# MCU_buck.net
KiCad netlist of a schematic drawn in Altium Designer
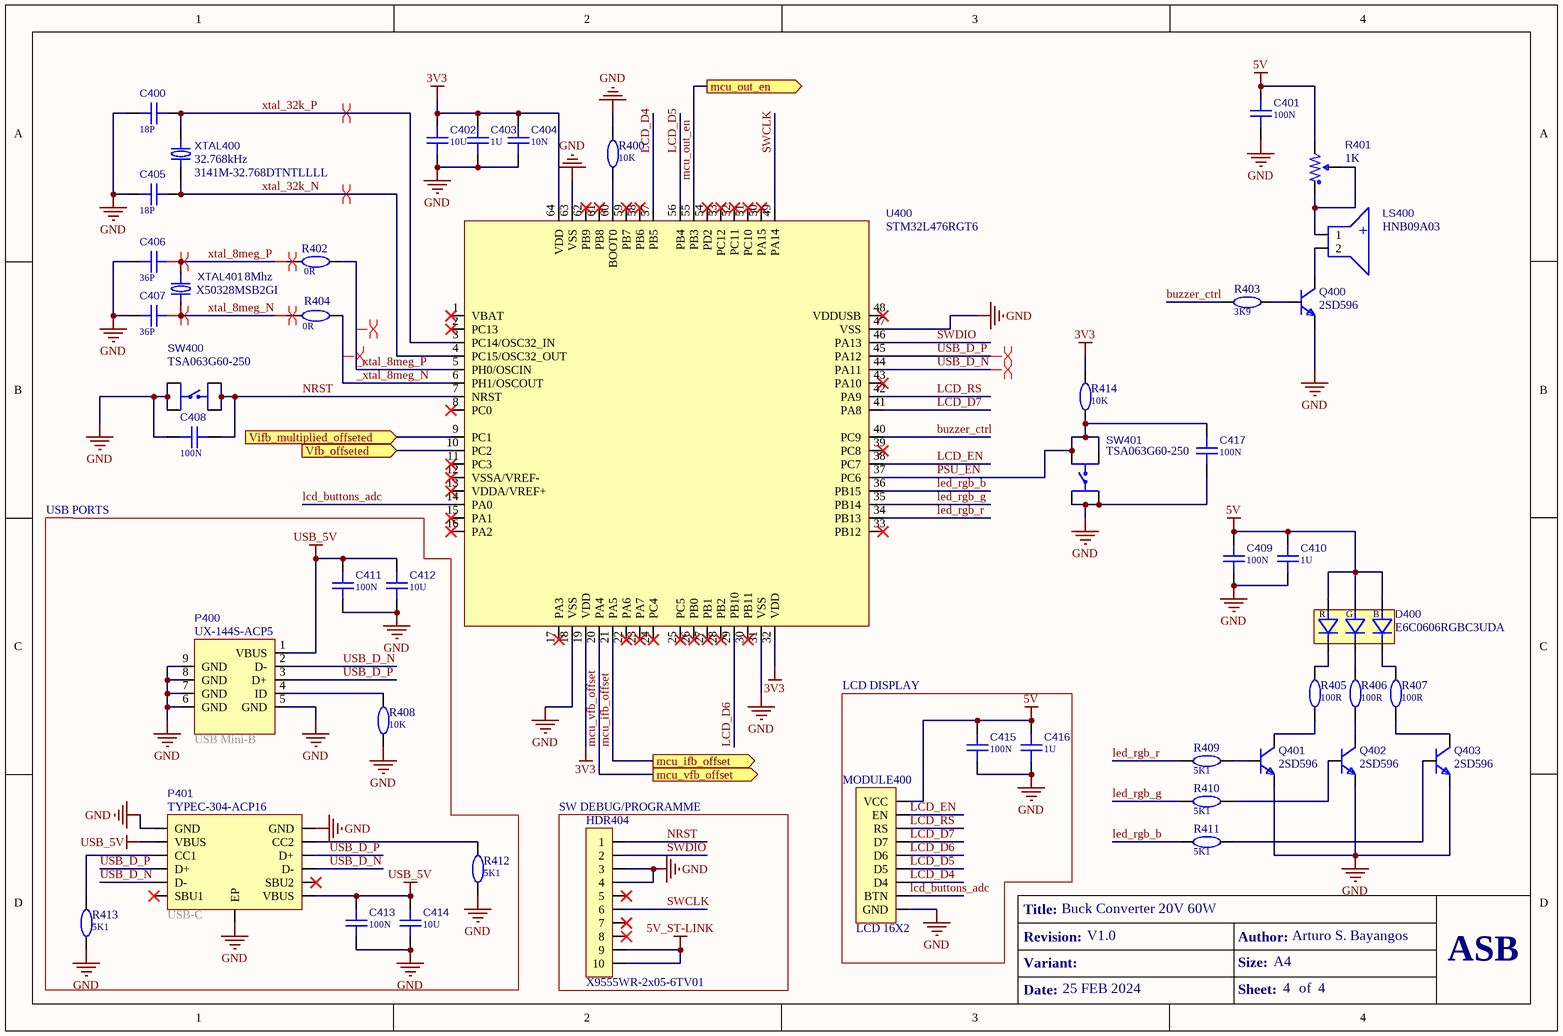
[diagram p0: MCU_buck.SchDoc]

(export (version "E")
  (design (tool "Eeschema 10.0.6"))
  (components
    (comp (ref "C400")
      (value "18P")
      (footprint "CAP_0603")
      (description "CAP 18P 0603 NPO 50V 5%")
      (fields (field (name "PART NUMBER") "CC0603JRNPO9BN180") (field (name "Comment") "CAPACITOR"))
      (libsource (lib "Altium_Library") (part "CAPACITOR"))
    )
    (comp (ref "C401")
      (value "100N")
      (footprint "CAP_0402")
      (description "CAP 100N 0402 X7R 50V 10%")
      (fields (field (name "PART NUMBER") "UMK105B7104KV-FR") (field (name "Comment") "CAPACITOR"))
      (libsource (lib "Altium_Library") (part "CAPACITOR"))
    )
    (comp (ref "C402")
      (value "10U")
      (footprint "CAP_1210")
      (description "CAP 10U 1210 X7R 50V 10%")
      (fields (field (name "PART NUMBER") "UMK325AB7106KM-T") (field (name "Comment") "CAPACITOR"))
      (libsource (lib "Altium_Library") (part "CAPACITOR"))
    )
    (comp (ref "C403")
      (value "1U")
      (footprint "CAP_0603")
      (description "CAP 1U 0603 X7R 25V 10%")
      (fields (field (name "PART NUMBER") "TMK107AB7105KAHT") (field (name "Comment") "CAPACITOR"))
      (libsource (lib "Altium_Library") (part "CAPACITOR"))
    )
    (comp (ref "C404")
      (value "10N")
      (footprint "CAP_0402")
      (description "CAP 10N 0402 X7R 50V 10%")
      (fields (field (name "PART NUMBER") "UMF105B7103KVHF") (field (name "Comment") "CAPACITOR"))
      (libsource (lib "Altium_Library") (part "CAPACITOR"))
    )
    (comp (ref "C405")
      (value "18P")
      (footprint "CAP_0603")
      (description "CAP 18P 0603 NPO 50V 5%")
      (fields (field (name "PART NUMBER") "CC0603JRNPO9BN180") (field (name "Comment") "CAPACITOR"))
      (libsource (lib "Altium_Library") (part "CAPACITOR"))
    )
    (comp (ref "C406")
      (value "36P")
      (footprint "CAP_0402")
      (description "CAP 36P 0402 NPO 50V 5%")
      (fields (field (name "PART NUMBER") "CC0603JRNPO9BN360") (field (name "Comment") "CAPACITOR"))
      (libsource (lib "Altium_Library") (part "CAPACITOR"))
    )
    (comp (ref "C407")
      (value "36P")
      (footprint "CAP_0402")
      (description "CAP 36P 0402 NPO 50V 5%")
      (fields (field (name "PART NUMBER") "CC0603JRNPO9BN360") (field (name "Comment") "CAPACITOR"))
      (libsource (lib "Altium_Library") (part "CAPACITOR"))
    )
    (comp (ref "C408")
      (value "100N")
      (footprint "CAP_0402")
      (description "CAP 100N 0402 X7R 50V 10%")
      (fields (field (name "PART NUMBER") "UMK105B7104KV-FR") (field (name "Comment") "CAPACITOR"))
      (libsource (lib "Altium_Library") (part "CAPACITOR"))
    )
    (comp (ref "C409")
      (value "100N")
      (footprint "CAP_0402")
      (description "CAP 100N 0402 X7R 50V 10%")
      (fields (field (name "PART NUMBER") "UMK105B7104KV-FR") (field (name "Comment") "CAPACITOR"))
      (libsource (lib "Altium_Library") (part "CAPACITOR"))
    )
    (comp (ref "C410")
      (value "1U")
      (footprint "CAP_0603")
      (description "CAP 1U 0603 X7R 25V 10%")
      (fields (field (name "PART NUMBER") "TMK107AB7105KAHT") (field (name "Comment") "CAPACITOR"))
      (libsource (lib "Altium_Library") (part "CAPACITOR"))
    )
    (comp (ref "C411")
      (value "100N")
      (footprint "CAP_0402")
      (description "CAP 100N 0402 X7R 50V 10%")
      (fields (field (name "PART NUMBER") "UMK105B7104KV-FR") (field (name "Comment") "CAPACITOR"))
      (libsource (lib "Altium_Library") (part "CAPACITOR"))
    )
    (comp (ref "C412")
      (value "10U")
      (footprint "CAP_1210")
      (description "CAP 10U 1210 X7R 50V 10%")
      (fields (field (name "PART NUMBER") "UMK325AB7106KM-T") (field (name "Comment") "CAPACITOR"))
      (libsource (lib "Altium_Library") (part "CAPACITOR"))
    )
    (comp (ref "C413")
      (value "100N")
      (footprint "CAP_0402")
      (description "CAP 100N 0402 X7R 50V 10%")
      (fields (field (name "PART NUMBER") "UMK105B7104KV-FR") (field (name "Comment") "CAPACITOR"))
      (libsource (lib "Altium_Library") (part "CAPACITOR"))
    )
    (comp (ref "C414")
      (value "10U")
      (footprint "CAP_1210")
      (description "CAP 10U 1210 X7R 50V 10%")
      (fields (field (name "PART NUMBER") "UMK325AB7106KM-T") (field (name "Comment") "CAPACITOR"))
      (libsource (lib "Altium_Library") (part "CAPACITOR"))
    )
    (comp (ref "C415")
      (value "100N")
      (footprint "CAP_0402")
      (description "CAP 100N 0402 X7R 50V 10%")
      (fields (field (name "PART NUMBER") "UMK105B7104KV-FR") (field (name "Comment") "CAPACITOR"))
      (libsource (lib "Altium_Library") (part "CAPACITOR"))
    )
    (comp (ref "C416")
      (value "1U")
      (footprint "CAP_0603")
      (description "CAP 1U 0603 X7R 25V 10%")
      (fields (field (name "PART NUMBER") "TMK107AB7105KAHT") (field (name "Comment") "CAPACITOR"))
      (libsource (lib "Altium_Library") (part "CAPACITOR"))
    )
    (comp (ref "C417")
      (value "100N")
      (footprint "CAP_0402")
      (description "CAP 100N 0402 X7R 50V 10%")
      (fields (field (name "PART NUMBER") "UMK105B7104KV-FR") (field (name "Comment") "CAPACITOR"))
      (libsource (lib "Altium_Library") (part "CAPACITOR"))
    )
    (comp (ref "D400")
      (value "E6C0606RGBC3UDA")
      (footprint "LED_0603")
      (description "LED E6C0606RGBC3UDA 0603 RGB 5V 20mA")
      (fields (field (name "VOLTAGE") "5V") (field (name "Comment") "LED_RGB_COMMON_P"))
      (libsource (lib "Altium_Library") (part "LED_RGB_COMMON_P"))
    )
    (comp (ref "HDR404")
      (value "X9555WR-2x05-6TV01")
      (footprint "SOCKET_2X5P_2.54mm_HORZ_X9555WR")
      (description "SOCKET \nX9555WR-2x05-6TV01 TH 2.54mm 2X5P HORZ")
      (fields (field (name "Comment") "HEADER_2X5P_2.54mm"))
      (libsource (lib "Altium_Library") (part "HEADER_2X5P_2.54mm"))
    )
    (comp (ref "LS400")
      (value "HNB09A03")
      (footprint "BUZZER_HNB09A03")
      (description "BUZZER HNB09A03 TH 1.5V-5V 3Khz")
      (fields (field (name "Comment") "BUZZER"))
      (libsource (lib "Altium_Library") (part "BUZZER"))
    )
    (comp (ref "MODULE400")
      (value "LCD 16X2")
      (footprint "LCD_MODULE_16X2")
      (description "LCD Display 16X2 Arduino Shield")
      (fields
        (field (name "PART NUMBER") "LCD_16X2_Arduino_Shield")
        (field (name "Comment") "LCD_MODULE_16X2")
      )
      (libsource (lib "Altium_Library") (part "LCD_MODULE_16X2"))
    )
    (comp (ref "P400")
      (value "UX-144S-ACP5")
      (footprint "USB_Mini-B_UX-144S-ACP5")
      (description "CONN UX-144S-ACP5 SMD USB_Mini-B 2.0")
      (fields (field (name "Comment") "USB_Mini-B"))
      (libsource (lib "Altium_Library") (part "USB_Mini-B"))
    )
    (comp (ref "P401")
      (value "TYPEC-304-ACP16")
      (footprint "USB-C_2.0_12PIN")
      (description "CONN TYPEC-304-ACP16 SMD USB-C 2.0")
      (fields (field (name "Comment") "USB-C_2.0"))
      (libsource (lib "Altium_Library") (part "USB-C_2.0"))
    )
    (comp (ref "Q400")
      (value "2SD596")
      (footprint "SOT-23")
      (description "NPN 2SD596 SOT-23 25V 0.2W")
      (fields (field (name "POWER") "0.2W") (field (name "Comment") "BJT_NPN"))
      (libsource (lib "Altium_Library") (part "BJT_NPN"))
    )
    (comp (ref "Q401")
      (value "2SD596")
      (footprint "SOT-23")
      (description "NPN 2SD596 SOT-23 25V 0.2W")
      (fields (field (name "POWER") "0.2W") (field (name "Comment") "BJT_NPN"))
      (libsource (lib "Altium_Library") (part "BJT_NPN"))
    )
    (comp (ref "Q402")
      (value "2SD596")
      (footprint "SOT-23")
      (description "NPN 2SD596 SOT-23 25V 0.2W")
      (fields (field (name "POWER") "0.2W") (field (name "Comment") "BJT_NPN"))
      (libsource (lib "Altium_Library") (part "BJT_NPN"))
    )
    (comp (ref "Q403")
      (value "2SD596")
      (footprint "SOT-23")
      (description "NPN 2SD596 SOT-23 25V 0.2W")
      (fields (field (name "POWER") "0.2W") (field (name "Comment") "BJT_NPN"))
      (libsource (lib "Altium_Library") (part "BJT_NPN"))
    )
    (comp (ref "R400")
      (value "10K")
      (footprint "RES_0603")
      (description "RES 10K 0603 0.1W 0.1% 75V")
      (fields (field (name "PART NUMBER") "ARG03BTC1002") (field (name "Comment") "RESISTOR"))
      (libsource (lib "Altium_Library") (part "RESISTOR"))
    )
    (comp (ref "R401")
      (value "1K")
      (footprint "RES_GF063P1-B102")
      (description "RES POT 1K TH 20%")
      (fields (field (name "PART NUMBER") "GF063P1-B102") (field (name "Comment") "RESISTOR_POT"))
      (libsource (lib "Altium_Library") (part "RESISTOR_POT"))
    )
    (comp (ref "R402")
      (value "0R")
      (footprint "RES_0402")
      (description "RES 0R 0402 1% 0.625W")
      (fields (field (name "PART NUMBER") "0402WGF0000TCE") (field (name "Comment") "RESISTOR"))
      (libsource (lib "Altium_Library") (part "RESISTOR"))
    )
    (comp (ref "R403")
      (value "3K9")
      (footprint "RES_0603")
      (description "RES 3K9 0603 1% 0.1W 75V")
      (fields (field (name "PART NUMBER") "RC0603FR-073K9L") (field (name "Comment") "RESISTOR"))
      (libsource (lib "Altium_Library") (part "RESISTOR"))
    )
    (comp (ref "R404")
      (value "0R")
      (footprint "RES_0402")
      (description "RES 0R 0402 1% 0.625W")
      (fields (field (name "PART NUMBER") "0402WGF0000TCE") (field (name "Comment") "RESISTOR"))
      (libsource (lib "Altium_Library") (part "RESISTOR"))
    )
    (comp (ref "R405")
      (value "100R")
      (footprint "RES_0603")
      (description "RES 100R 00603 0.1W 0.25% 75V")
      (fields (field (name "PART NUMBER") "RT0603CRE07100RL") (field (name "Comment") "RESISTOR"))
      (libsource (lib "Altium_Library") (part "RESISTOR"))
    )
    (comp (ref "R406")
      (value "100R")
      (footprint "RES_0603")
      (description "RES 100R 00603 0.1W 0.25% 75V")
      (fields (field (name "PART NUMBER") "RT0603CRE07100RL") (field (name "Comment") "RESISTOR"))
      (libsource (lib "Altium_Library") (part "RESISTOR"))
    )
    (comp (ref "R407")
      (value "100R")
      (footprint "RES_0603")
      (description "RES 100R 00603 0.1W 0.25% 75V")
      (fields (field (name "PART NUMBER") "RT0603CRE07100RL") (field (name "Comment") "RESISTOR"))
      (libsource (lib "Altium_Library") (part "RESISTOR"))
    )
    (comp (ref "R408")
      (value "10K")
      (footprint "RES_0603")
      (description "RES 10K 0603 0.1W 0.1% 75V")
      (fields (field (name "PART NUMBER") "ARG03BTC1002") (field (name "Comment") "RESISTOR"))
      (libsource (lib "Altium_Library") (part "RESISTOR"))
    )
    (comp (ref "R409")
      (value "5K1")
      (footprint "RES_0402")
      (description "RES 5K1 0402 1% 0.625W 50V")
      (fields (field (name "PART NUMBER") "RC0402FR-075K1L") (field (name "Comment") "RESISTOR"))
      (libsource (lib "Altium_Library") (part "RESISTOR"))
    )
    (comp (ref "R410")
      (value "5K1")
      (footprint "RES_0402")
      (description "RES 5K1 0402 1% 0.625W 50V")
      (fields (field (name "PART NUMBER") "RC0402FR-075K1L") (field (name "Comment") "RESISTOR"))
      (libsource (lib "Altium_Library") (part "RESISTOR"))
    )
    (comp (ref "R411")
      (value "5K1")
      (footprint "RES_0402")
      (description "RES 5K1 0402 1% 0.625W 50V")
      (fields (field (name "PART NUMBER") "RC0402FR-075K1L") (field (name "Comment") "RESISTOR"))
      (libsource (lib "Altium_Library") (part "RESISTOR"))
    )
    (comp (ref "R412")
      (value "5K1")
      (footprint "RES_0402")
      (description "RES 5K1 0402 1% 0.625W 50V")
      (fields (field (name "PART NUMBER") "RC0402FR-075K1L") (field (name "Comment") "RESISTOR"))
      (libsource (lib "Altium_Library") (part "RESISTOR"))
    )
    (comp (ref "R413")
      (value "5K1")
      (footprint "RES_0402")
      (description "RES 5K1 0402 1% 0.625W 50V")
      (fields (field (name "PART NUMBER") "RC0402FR-075K1L") (field (name "Comment") "RESISTOR"))
      (libsource (lib "Altium_Library") (part "RESISTOR"))
    )
    (comp (ref "R414")
      (value "10K")
      (footprint "RES_0603")
      (description "RES 10K 0603 0.1W 0.1% 75V")
      (fields (field (name "PART NUMBER") "ARG03BTC1002") (field (name "Comment") "RESISTOR"))
      (libsource (lib "Altium_Library") (part "RESISTOR"))
    )
    (comp (ref "SW400")
      (value "TSA063G60-250")
      (footprint "SMD_TSA063G60-250")
      (description "SW \nTSA063G60-250 SMD SPST 50mA 12V")
      (fields (field (name "VOLTAGE") "12V") (field (name "Comment") "SWITCH_SPST"))
      (libsource (lib "Altium_Library") (part "SWITCH_SPST"))
    )
    (comp (ref "SW401")
      (value "TSA063G60-250")
      (footprint "SMD_TSA063G60-250")
      (description "SW \nTSA063G60-250 SMD SPST 50mA 12V")
      (fields (field (name "VOLTAGE") "12V") (field (name "Comment") "SWITCH_SPST"))
      (libsource (lib "Altium_Library") (part "SWITCH_SPST"))
    )
    (comp (ref "U400")
      (value "STM32L476RGT6")
      (footprint "LQFP-64")
      (description "IC STM32L476RGT6 LQFP-64 MCU")
      (fields (field (name "Comment") "MCU_STM32L476RGT6"))
      (libsource (lib "Altium_Library") (part "MCU_STM32L476RGT6"))
    )
    (comp (ref "XTAL400")
      (value "3141M-32.768DTNTLLLL")
      (footprint "SMD_W1.5mm_L4.1mm_3141M-32.768DTNTLLLL")
      (description "XTAL 3141M-32.768DTNTLLLL SMD_W1.5mm_L4.1mm 32.768kHz 12.5pF")
      (fields (field (name "FREQUENCY") "32.768kHz") (field (name "Comment") "XTAL"))
      (libsource (lib "Altium_Library") (part "XTAL"))
    )
    (comp (ref "XTAL401")
      (value "X50328MSB2GI")
      (footprint "SMD_W3.2mm_L5.0m_X50328MSB2GI")
      (description "XTAL \nX50328MSB2GI SMD_W3.2mm_L5.0mm 8Mhz 20pF")
      (fields (field (name "FREQUENCY") "8Mhz") (field (name "Comment") "XTAL"))
      (libsource (lib "Altium_Library") (part "XTAL"))
    )
  )
  (nets
    (net (code "1") (name "/LCD_D4") (class "Default")
      (node (ref "MODULE400") (pin "17") (pinfunction "D4_17") (pintype "passive"))
      (node (ref "U400") (pin "57") (pinfunction "PB5_57") (pintype "passive"))
    )
    (net (code "2") (name "/LCD_D5") (class "Default")
      (node (ref "MODULE400") (pin "18") (pinfunction "D5_18") (pintype "passive"))
      (node (ref "U400") (pin "56") (pinfunction "PB4_56") (pintype "passive"))
    )
    (net (code "3") (name "/LCD_D6") (class "Default")
      (node (ref "MODULE400") (pin "19") (pinfunction "D6_19") (pintype "passive"))
      (node (ref "U400") (pin "29") (pinfunction "PB10_29") (pintype "passive"))
    )
    (net (code "4") (name "/LCD_D7") (class "Default")
      (node (ref "MODULE400") (pin "20") (pinfunction "D7_20") (pintype "passive"))
      (node (ref "U400") (pin "41") (pinfunction "PA8_41") (pintype "passive"))
    )
    (net (code "5") (name "/LCD_EN") (class "Default")
      (node (ref "MODULE400") (pin "22") (pinfunction "EN_22") (pintype "passive"))
      (node (ref "U400") (pin "38") (pinfunction "PC7_38") (pintype "passive"))
    )
    (net (code "6") (name "/LCD_RS") (class "Default")
      (node (ref "MODULE400") (pin "21") (pinfunction "RS_21") (pintype "passive"))
      (node (ref "U400") (pin "42") (pinfunction "PA9_42") (pintype "passive"))
    )
    (net (code "7") (name "/NRST") (class "Default")
      (node (ref "C408") (pin "2") (pinfunction "2_2") (pintype "passive"))
      (node (ref "HDR404") (pin "1") (pinfunction "1_1") (pintype "passive"))
      (node (ref "SW400") (pin "1") (pinfunction "1_1") (pintype "passive"))
      (node (ref "SW400") (pin "2") (pinfunction "2_2") (pintype "passive"))
      (node (ref "U400") (pin "7") (pinfunction "NRST_7") (pintype "passive"))
    )
    (net (code "8") (name "/PSU_EN") (class "Default")
      (node (ref "C417") (pin "1") (pinfunction "1_1") (pintype "passive"))
      (node (ref "R414") (pin "1") (pinfunction "1_1") (pintype "passive"))
      (node (ref "SW401") (pin "1") (pinfunction "1_1") (pintype "passive"))
      (node (ref "SW401") (pin "2") (pinfunction "2_2") (pintype "passive"))
      (node (ref "U400") (pin "37") (pinfunction "PC6_37") (pintype "passive"))
    )
    (net (code "9") (name "/SWCLK") (class "Default")
      (node (ref "HDR404") (pin "6") (pinfunction "6_6") (pintype "passive"))
      (node (ref "U400") (pin "49") (pinfunction "PA14_49") (pintype "passive"))
    )
    (net (code "10") (name "/SWDIO") (class "Default")
      (node (ref "HDR404") (pin "2") (pinfunction "2_2") (pintype "passive"))
      (node (ref "U400") (pin "46") (pinfunction "PA13_46") (pintype "passive"))
    )
    (net (code "11") (name "/USB_D_N") (class "Default")
      (node (ref "P400") (pin "2") (pinfunction "D-_2") (pintype "passive"))
      (node (ref "P401") (pin "A7") (pinfunction "D-_A7") (pintype "passive"))
      (node (ref "P401") (pin "B7") (pinfunction "D-_B7") (pintype "passive"))
      (node (ref "U400") (pin "44") (pinfunction "PA11_44") (pintype "passive"))
    )
    (net (code "12") (name "/USB_D_P") (class "Default")
      (node (ref "P400") (pin "3") (pinfunction "D+_3") (pintype "passive"))
      (node (ref "P401") (pin "A6") (pinfunction "D+_A6") (pintype "passive"))
      (node (ref "P401") (pin "B6") (pinfunction "D+_B6") (pintype "passive"))
      (node (ref "U400") (pin "45") (pinfunction "PA12_45") (pintype "passive"))
    )
    (net (code "13") (name "/Vfb_offseted") (class "Default")
      (node (ref "U400") (pin "10") (pinfunction "PC2_10") (pintype "passive"))
    )
    (net (code "14") (name "/Vifb_multiplied_offseted") (class "Default")
      (node (ref "U400") (pin "9") (pinfunction "PC1_9") (pintype "passive"))
    )
    (net (code "15") (name "/_xtal_8meg_N") (class "Default")
      (node (ref "R404") (pin "2") (pinfunction "2_2") (pintype "passive"))
      (node (ref "U400") (pin "6") (pinfunction "PH1/OSCOUT_6") (pintype "passive"))
    )
    (net (code "16") (name "/_xtal_8meg_P") (class "Default")
      (node (ref "R402") (pin "2") (pinfunction "2_2") (pintype "passive"))
      (node (ref "U400") (pin "5") (pinfunction "PH0/OSCIN_5") (pintype "passive"))
    )
    (net (code "17") (name "/buzzer_ctrl") (class "Default")
      (node (ref "R403") (pin "1") (pinfunction "1_1") (pintype "passive"))
      (node (ref "U400") (pin "40") (pinfunction "PC9_40") (pintype "passive"))
    )
    (net (code "18") (name "/lcd_buttons_adc") (class "Default")
      (node (ref "MODULE400") (pin "7") (pinfunction "BTN_7") (pintype "passive"))
      (node (ref "U400") (pin "14") (pinfunction "PA0_14") (pintype "passive"))
    )
    (net (code "19") (name "/led_rgb_b") (class "Default")
      (node (ref "R411") (pin "1") (pinfunction "1_1") (pintype "passive"))
      (node (ref "U400") (pin "36") (pinfunction "PB15_36") (pintype "passive"))
    )
    (net (code "20") (name "/led_rgb_g") (class "Default")
      (node (ref "R410") (pin "1") (pinfunction "1_1") (pintype "passive"))
      (node (ref "U400") (pin "35") (pinfunction "PB14_35") (pintype "passive"))
    )
    (net (code "21") (name "/led_rgb_r") (class "Default")
      (node (ref "R409") (pin "1") (pinfunction "1_1") (pintype "passive"))
      (node (ref "U400") (pin "34") (pinfunction "PB13_34") (pintype "passive"))
    )
    (net (code "22") (name "/mcu_ifb_offset") (class "Default")
      (node (ref "U400") (pin "21") (pinfunction "PA5_21") (pintype "passive"))
    )
    (net (code "23") (name "/mcu_out_en") (class "Default")
      (node (ref "U400") (pin "55") (pinfunction "PB3_55") (pintype "passive"))
    )
    (net (code "24") (name "/mcu_vfb_offset") (class "Default")
      (node (ref "U400") (pin "20") (pinfunction "PA4_20") (pintype "passive"))
    )
    (net (code "25") (name "/xtal_8meg_N") (class "Default")
      (node (ref "C407") (pin "2") (pinfunction "2_2") (pintype "passive"))
      (node (ref "R404") (pin "1") (pinfunction "1_1") (pintype "passive"))
      (node (ref "XTAL401") (pin "1") (pinfunction "1_1") (pintype "passive"))
    )
    (net (code "26") (name "/xtal_8meg_P") (class "Default")
      (node (ref "C406") (pin "2") (pinfunction "2_2") (pintype "passive"))
      (node (ref "R402") (pin "1") (pinfunction "1_1") (pintype "passive"))
      (node (ref "XTAL401") (pin "2") (pinfunction "2_2") (pintype "passive"))
    )
    (net (code "27") (name "/xtal_32k_N") (class "Default")
      (node (ref "C405") (pin "2") (pinfunction "2_2") (pintype "passive"))
      (node (ref "U400") (pin "4") (pinfunction "PC15/OSC32_OUT_4") (pintype "passive"))
      (node (ref "XTAL400") (pin "2") (pinfunction "2_2") (pintype "passive"))
    )
    (net (code "28") (name "/xtal_32k_P") (class "Default")
      (node (ref "C400") (pin "2") (pinfunction "2_2") (pintype "passive"))
      (node (ref "U400") (pin "3") (pinfunction "PC14/OSC32_IN_3") (pintype "passive"))
      (node (ref "XTAL400") (pin "1") (pinfunction "1_1") (pintype "passive"))
    )
    (net (code "29") (name "3V3") (class "Default")
      (node (ref "C402") (pin "2") (pinfunction "2_2") (pintype "passive"))
      (node (ref "C403") (pin "2") (pinfunction "2_2") (pintype "passive"))
      (node (ref "C404") (pin "2") (pinfunction "2_2") (pintype "passive"))
      (node (ref "R414") (pin "2") (pinfunction "2_2") (pintype "passive"))
      (node (ref "U400") (pin "19") (pinfunction "VDD_19") (pintype "passive"))
      (node (ref "U400") (pin "32") (pinfunction "VDD_32") (pintype "passive"))
      (node (ref "U400") (pin "64") (pinfunction "VDD_64") (pintype "passive"))
    )
    (net (code "30") (name "5V") (class "Default")
      (node (ref "C401") (pin "2") (pinfunction "2_2") (pintype "passive"))
      (node (ref "C409") (pin "2") (pinfunction "2_2") (pintype "passive"))
      (node (ref "C410") (pin "2") (pinfunction "2_2") (pintype "passive"))
      (node (ref "C415") (pin "2") (pinfunction "2_2") (pintype "passive"))
      (node (ref "C416") (pin "2") (pinfunction "2_2") (pintype "passive"))
      (node (ref "D400") (pin "2") (pinfunction "P_2") (pintype "passive"))
      (node (ref "MODULE400") (pin "5") (pinfunction "VCC_5") (pintype "passive"))
      (node (ref "R401") (pin "3") (pinfunction "3_3") (pintype "passive"))
    )
    (net (code "31") (name "5V_ST-LINK") (class "Default")
      (node (ref "HDR404") (pin "10") (pinfunction "10_10") (pintype "passive"))
      (node (ref "HDR404") (pin "9") (pinfunction "9_9") (pintype "passive"))
    )
    (net (code "32") (name "GND") (class "Default")
      (node (ref "C400") (pin "1") (pinfunction "1_1") (pintype "passive"))
      (node (ref "C401") (pin "1") (pinfunction "1_1") (pintype "passive"))
      (node (ref "C402") (pin "1") (pinfunction "1_1") (pintype "passive"))
      (node (ref "C403") (pin "1") (pinfunction "1_1") (pintype "passive"))
      (node (ref "C404") (pin "1") (pinfunction "1_1") (pintype "passive"))
      (node (ref "C405") (pin "1") (pinfunction "1_1") (pintype "passive"))
      (node (ref "C406") (pin "1") (pinfunction "1_1") (pintype "passive"))
      (node (ref "C407") (pin "1") (pinfunction "1_1") (pintype "passive"))
      (node (ref "C408") (pin "1") (pinfunction "1_1") (pintype "passive"))
      (node (ref "C409") (pin "1") (pinfunction "1_1") (pintype "passive"))
      (node (ref "C410") (pin "1") (pinfunction "1_1") (pintype "passive"))
      (node (ref "C411") (pin "1") (pinfunction "1_1") (pintype "passive"))
      (node (ref "C412") (pin "1") (pinfunction "1_1") (pintype "passive"))
      (node (ref "C413") (pin "1") (pinfunction "1_1") (pintype "passive"))
      (node (ref "C414") (pin "1") (pinfunction "1_1") (pintype "passive"))
      (node (ref "C415") (pin "1") (pinfunction "1_1") (pintype "passive"))
      (node (ref "C416") (pin "1") (pinfunction "1_1") (pintype "passive"))
      (node (ref "C417") (pin "2") (pinfunction "2_2") (pintype "passive"))
      (node (ref "HDR404") (pin "3") (pinfunction "3_3") (pintype "passive"))
      (node (ref "HDR404") (pin "4") (pinfunction "4_4") (pintype "passive"))
      (node (ref "MODULE400") (pin "6") (pinfunction "GND_6") (pintype "passive"))
      (node (ref "P400") (pin "5") (pinfunction "GND_5") (pintype "passive"))
      (node (ref "P400") (pin "6") (pinfunction "GND_6") (pintype "passive"))
      (node (ref "P400") (pin "7") (pinfunction "GND_7") (pintype "passive"))
      (node (ref "P400") (pin "8") (pinfunction "GND_8") (pintype "passive"))
      (node (ref "P400") (pin "9") (pinfunction "GND_9") (pintype "passive"))
      (node (ref "P401") (pin "A1B12") (pinfunction "GND_A1B12") (pintype "passive"))
      (node (ref "P401") (pin "B1A12") (pinfunction "GND_B1A12") (pintype "passive"))
      (node (ref "P401") (pin "EP") (pinfunction "EP_EP") (pintype "passive"))
      (node (ref "Q400") (pin "2") (pinfunction "E_2") (pintype "passive"))
      (node (ref "Q401") (pin "2") (pinfunction "E_2") (pintype "passive"))
      (node (ref "Q402") (pin "2") (pinfunction "E_2") (pintype "passive"))
      (node (ref "Q403") (pin "2") (pinfunction "E_2") (pintype "passive"))
      (node (ref "R400") (pin "2") (pinfunction "2_2") (pintype "passive"))
      (node (ref "R408") (pin "1") (pinfunction "1_1") (pintype "passive"))
      (node (ref "R412") (pin "2") (pinfunction "2_2") (pintype "passive"))
      (node (ref "R413") (pin "2") (pinfunction "2_2") (pintype "passive"))
      (node (ref "SW400") (pin "3") (pinfunction "3_3") (pintype "passive"))
      (node (ref "SW400") (pin "4") (pinfunction "4_4") (pintype "passive"))
      (node (ref "SW401") (pin "3") (pinfunction "3_3") (pintype "passive"))
      (node (ref "SW401") (pin "4") (pinfunction "4_4") (pintype "passive"))
      (node (ref "U400") (pin "18") (pinfunction "VSS_18") (pintype "passive"))
      (node (ref "U400") (pin "31") (pinfunction "VSS_31") (pintype "passive"))
      (node (ref "U400") (pin "47") (pinfunction "VSS_47") (pintype "passive"))
      (node (ref "U400") (pin "63") (pinfunction "VSS_63") (pintype "passive"))
    )
    (net (code "33") (name "Net-(D400-B)") (class "Default")
      (node (ref "D400") (pin "1") (pinfunction "B_1") (pintype "passive"))
      (node (ref "R407") (pin "2") (pinfunction "2_2") (pintype "passive"))
    )
    (net (code "34") (name "Net-(D400-G)") (class "Default")
      (node (ref "D400") (pin "3") (pinfunction "G_3") (pintype "passive"))
      (node (ref "R406") (pin "2") (pinfunction "2_2") (pintype "passive"))
    )
    (net (code "35") (name "Net-(D400-R)") (class "Default")
      (node (ref "D400") (pin "4") (pinfunction "R_4") (pintype "passive"))
      (node (ref "R405") (pin "2") (pinfunction "2_2") (pintype "passive"))
    )
    (net (code "36") (name "Net-(LS400-Pad1)") (class "Default")
      (node (ref "LS400") (pin "1") (pinfunction "1_1") (pintype "passive"))
      (node (ref "R401") (pin "1") (pinfunction "1_1") (pintype "passive"))
      (node (ref "R401") (pin "2") (pinfunction "2_2") (pintype "passive"))
    )
    (net (code "37") (name "Net-(P400-ID)") (class "Default")
      (node (ref "P400") (pin "4") (pinfunction "ID_4") (pintype "passive"))
      (node (ref "R408") (pin "2") (pinfunction "2_2") (pintype "passive"))
    )
    (net (code "38") (name "Net-(P401-CC1)") (class "Default")
      (node (ref "P401") (pin "A5") (pinfunction "CC1_A5") (pintype "passive"))
      (node (ref "R413") (pin "1") (pinfunction "1_1") (pintype "passive"))
    )
    (net (code "39") (name "Net-(P401-CC2)") (class "Default")
      (node (ref "P401") (pin "B5") (pinfunction "CC2_B5") (pintype "passive"))
      (node (ref "R412") (pin "1") (pinfunction "1_1") (pintype "passive"))
    )
    (net (code "40") (name "Net-(Q400-B)") (class "Default")
      (node (ref "Q400") (pin "1") (pinfunction "B_1") (pintype "passive"))
      (node (ref "R403") (pin "2") (pinfunction "2_2") (pintype "passive"))
    )
    (net (code "41") (name "Net-(Q400-C)") (class "Default")
      (node (ref "LS400") (pin "2") (pinfunction "2_2") (pintype "passive"))
      (node (ref "Q400") (pin "3") (pinfunction "C_3") (pintype "passive"))
    )
    (net (code "42") (name "Net-(Q401-B)") (class "Default")
      (node (ref "Q401") (pin "1") (pinfunction "B_1") (pintype "passive"))
      (node (ref "R409") (pin "2") (pinfunction "2_2") (pintype "passive"))
    )
    (net (code "43") (name "Net-(Q401-C)") (class "Default")
      (node (ref "Q401") (pin "3") (pinfunction "C_3") (pintype "passive"))
      (node (ref "R405") (pin "1") (pinfunction "1_1") (pintype "passive"))
    )
    (net (code "44") (name "Net-(Q402-B)") (class "Default")
      (node (ref "Q402") (pin "1") (pinfunction "B_1") (pintype "passive"))
      (node (ref "R410") (pin "2") (pinfunction "2_2") (pintype "passive"))
    )
    (net (code "45") (name "Net-(Q402-C)") (class "Default")
      (node (ref "Q402") (pin "3") (pinfunction "C_3") (pintype "passive"))
      (node (ref "R406") (pin "1") (pinfunction "1_1") (pintype "passive"))
    )
    (net (code "46") (name "Net-(Q403-B)") (class "Default")
      (node (ref "Q403") (pin "1") (pinfunction "B_1") (pintype "passive"))
      (node (ref "R411") (pin "2") (pinfunction "2_2") (pintype "passive"))
    )
    (net (code "47") (name "Net-(Q403-C)") (class "Default")
      (node (ref "Q403") (pin "3") (pinfunction "C_3") (pintype "passive"))
      (node (ref "R407") (pin "1") (pinfunction "1_1") (pintype "passive"))
    )
    (net (code "48") (name "Net-(U400-BOOT0)") (class "Default")
      (node (ref "R400") (pin "1") (pinfunction "1_1") (pintype "passive"))
      (node (ref "U400") (pin "60") (pinfunction "BOOT0_60") (pintype "passive"))
    )
    (net (code "49") (name "USB_5V") (class "Default")
      (node (ref "C411") (pin "2") (pinfunction "2_2") (pintype "passive"))
      (node (ref "C412") (pin "2") (pinfunction "2_2") (pintype "passive"))
      (node (ref "C413") (pin "2") (pinfunction "2_2") (pintype "passive"))
      (node (ref "C414") (pin "2") (pinfunction "2_2") (pintype "passive"))
      (node (ref "P400") (pin "1") (pinfunction "VBUS_1") (pintype "passive"))
      (node (ref "P401") (pin "A4B9") (pinfunction "VBUS_A4B9") (pintype "passive"))
      (node (ref "P401") (pin "B4A9") (pinfunction "VBUS_B4A9") (pintype "passive"))
    )
    (net (code "50") (name "unconnected-(HDR404-Pad5)") (class "Default")
      (node (ref "HDR404") (pin "5") (pinfunction "5_5") (pintype "passive+no_connect"))
    )
    (net (code "51") (name "unconnected-(HDR404-Pad7)") (class "Default")
      (node (ref "HDR404") (pin "7") (pinfunction "7_7") (pintype "passive+no_connect"))
    )
    (net (code "52") (name "unconnected-(HDR404-Pad8)") (class "Default")
      (node (ref "HDR404") (pin "8") (pinfunction "8_8") (pintype "passive+no_connect"))
    )
    (net (code "53") (name "unconnected-(P401-SBU1-PadA8)") (class "Default")
      (node (ref "P401") (pin "A8") (pinfunction "SBU1_A8") (pintype "passive+no_connect"))
    )
    (net (code "54") (name "unconnected-(P401-SBU2-PadB8)") (class "Default")
      (node (ref "P401") (pin "B8") (pinfunction "SBU2_B8") (pintype "passive+no_connect"))
    )
    (net (code "55") (name "unconnected-(U400-PA1-Pad15)") (class "Default")
      (node (ref "U400") (pin "15") (pinfunction "PA1_15") (pintype "passive+no_connect"))
    )
    (net (code "56") (name "unconnected-(U400-PA2-Pad16)") (class "Default")
      (node (ref "U400") (pin "16") (pinfunction "PA2_16") (pintype "passive+no_connect"))
    )
    (net (code "57") (name "unconnected-(U400-PA3-Pad17)") (class "Default")
      (node (ref "U400") (pin "17") (pinfunction "PA3_17") (pintype "passive+no_connect"))
    )
    (net (code "58") (name "unconnected-(U400-PA6-Pad22)") (class "Default")
      (node (ref "U400") (pin "22") (pinfunction "PA6_22") (pintype "passive+no_connect"))
    )
    (net (code "59") (name "unconnected-(U400-PA7-Pad23)") (class "Default")
      (node (ref "U400") (pin "23") (pinfunction "PA7_23") (pintype "passive+no_connect"))
    )
    (net (code "60") (name "unconnected-(U400-PA10-Pad43)") (class "Default")
      (node (ref "U400") (pin "43") (pinfunction "PA10_43") (pintype "passive+no_connect"))
    )
    (net (code "61") (name "unconnected-(U400-PA15-Pad50)") (class "Default")
      (node (ref "U400") (pin "50") (pinfunction "PA15_50") (pintype "passive+no_connect"))
    )
    (net (code "62") (name "unconnected-(U400-PB0-Pad26)") (class "Default")
      (node (ref "U400") (pin "26") (pinfunction "PB0_26") (pintype "passive+no_connect"))
    )
    (net (code "63") (name "unconnected-(U400-PB1-Pad27)") (class "Default")
      (node (ref "U400") (pin "27") (pinfunction "PB1_27") (pintype "passive+no_connect"))
    )
    (net (code "64") (name "unconnected-(U400-PB2-Pad28)") (class "Default")
      (node (ref "U400") (pin "28") (pinfunction "PB2_28") (pintype "passive+no_connect"))
    )
    (net (code "65") (name "unconnected-(U400-PB6-Pad58)") (class "Default")
      (node (ref "U400") (pin "58") (pinfunction "PB6_58") (pintype "passive+no_connect"))
    )
    (net (code "66") (name "unconnected-(U400-PB7-Pad59)") (class "Default")
      (node (ref "U400") (pin "59") (pinfunction "PB7_59") (pintype "passive+no_connect"))
    )
    (net (code "67") (name "unconnected-(U400-PB8-Pad61)") (class "Default")
      (node (ref "U400") (pin "61") (pinfunction "PB8_61") (pintype "passive+no_connect"))
    )
    (net (code "68") (name "unconnected-(U400-PB9-Pad62)") (class "Default")
      (node (ref "U400") (pin "62") (pinfunction "PB9_62") (pintype "passive+no_connect"))
    )
    (net (code "69") (name "unconnected-(U400-PB11-Pad30)") (class "Default")
      (node (ref "U400") (pin "30") (pinfunction "PB11_30") (pintype "passive+no_connect"))
    )
    (net (code "70") (name "unconnected-(U400-PB12-Pad33)") (class "Default")
      (node (ref "U400") (pin "33") (pinfunction "PB12_33") (pintype "passive+no_connect"))
    )
    (net (code "71") (name "unconnected-(U400-PC0-Pad8)") (class "Default")
      (node (ref "U400") (pin "8") (pinfunction "PC0_8") (pintype "passive+no_connect"))
    )
    (net (code "72") (name "unconnected-(U400-PC3-Pad11)") (class "Default")
      (node (ref "U400") (pin "11") (pinfunction "PC3_11") (pintype "passive+no_connect"))
    )
    (net (code "73") (name "unconnected-(U400-PC4-Pad24)") (class "Default")
      (node (ref "U400") (pin "24") (pinfunction "PC4_24") (pintype "passive+no_connect"))
    )
    (net (code "74") (name "unconnected-(U400-PC5-Pad25)") (class "Default")
      (node (ref "U400") (pin "25") (pinfunction "PC5_25") (pintype "passive+no_connect"))
    )
    (net (code "75") (name "unconnected-(U400-PC8-Pad39)") (class "Default")
      (node (ref "U400") (pin "39") (pinfunction "PC8_39") (pintype "passive+no_connect"))
    )
    (net (code "76") (name "unconnected-(U400-PC10-Pad51)") (class "Default")
      (node (ref "U400") (pin "51") (pinfunction "PC10_51") (pintype "passive+no_connect"))
    )
    (net (code "77") (name "unconnected-(U400-PC11-Pad52)") (class "Default")
      (node (ref "U400") (pin "52") (pinfunction "PC11_52") (pintype "passive+no_connect"))
    )
    (net (code "78") (name "unconnected-(U400-PC12-Pad53)") (class "Default")
      (node (ref "U400") (pin "53") (pinfunction "PC12_53") (pintype "passive+no_connect"))
    )
    (net (code "79") (name "unconnected-(U400-PC13-Pad2)") (class "Default")
      (node (ref "U400") (pin "2") (pinfunction "PC13_2") (pintype "passive+no_connect"))
    )
    (net (code "80") (name "unconnected-(U400-PD2-Pad54)") (class "Default")
      (node (ref "U400") (pin "54") (pinfunction "PD2_54") (pintype "passive+no_connect"))
    )
    (net (code "81") (name "unconnected-(U400-VBAT-Pad1)") (class "Default")
      (node (ref "U400") (pin "1") (pinfunction "VBAT_1") (pintype "passive+no_connect"))
    )
    (net (code "82") (name "unconnected-(U400-VDDA{slash}VREF+-Pad13)") (class "Default")
      (node (ref "U400") (pin "13") (pinfunction "VDDA/VREF+_13") (pintype "passive+no_connect"))
    )
    (net (code "83") (name "unconnected-(U400-VDDUSB-Pad48)") (class "Default")
      (node (ref "U400") (pin "48") (pinfunction "VDDUSB_48") (pintype "passive+no_connect"))
    )
    (net (code "84") (name "unconnected-(U400-VSSA{slash}VREF--Pad12)") (class "Default")
      (node (ref "U400") (pin "12") (pinfunction "VSSA/VREF-_12") (pintype "passive+no_connect"))
    )
  )
)
